# FMC_connector.net
KiCad netlist of a schematic drawn in Altium Designer
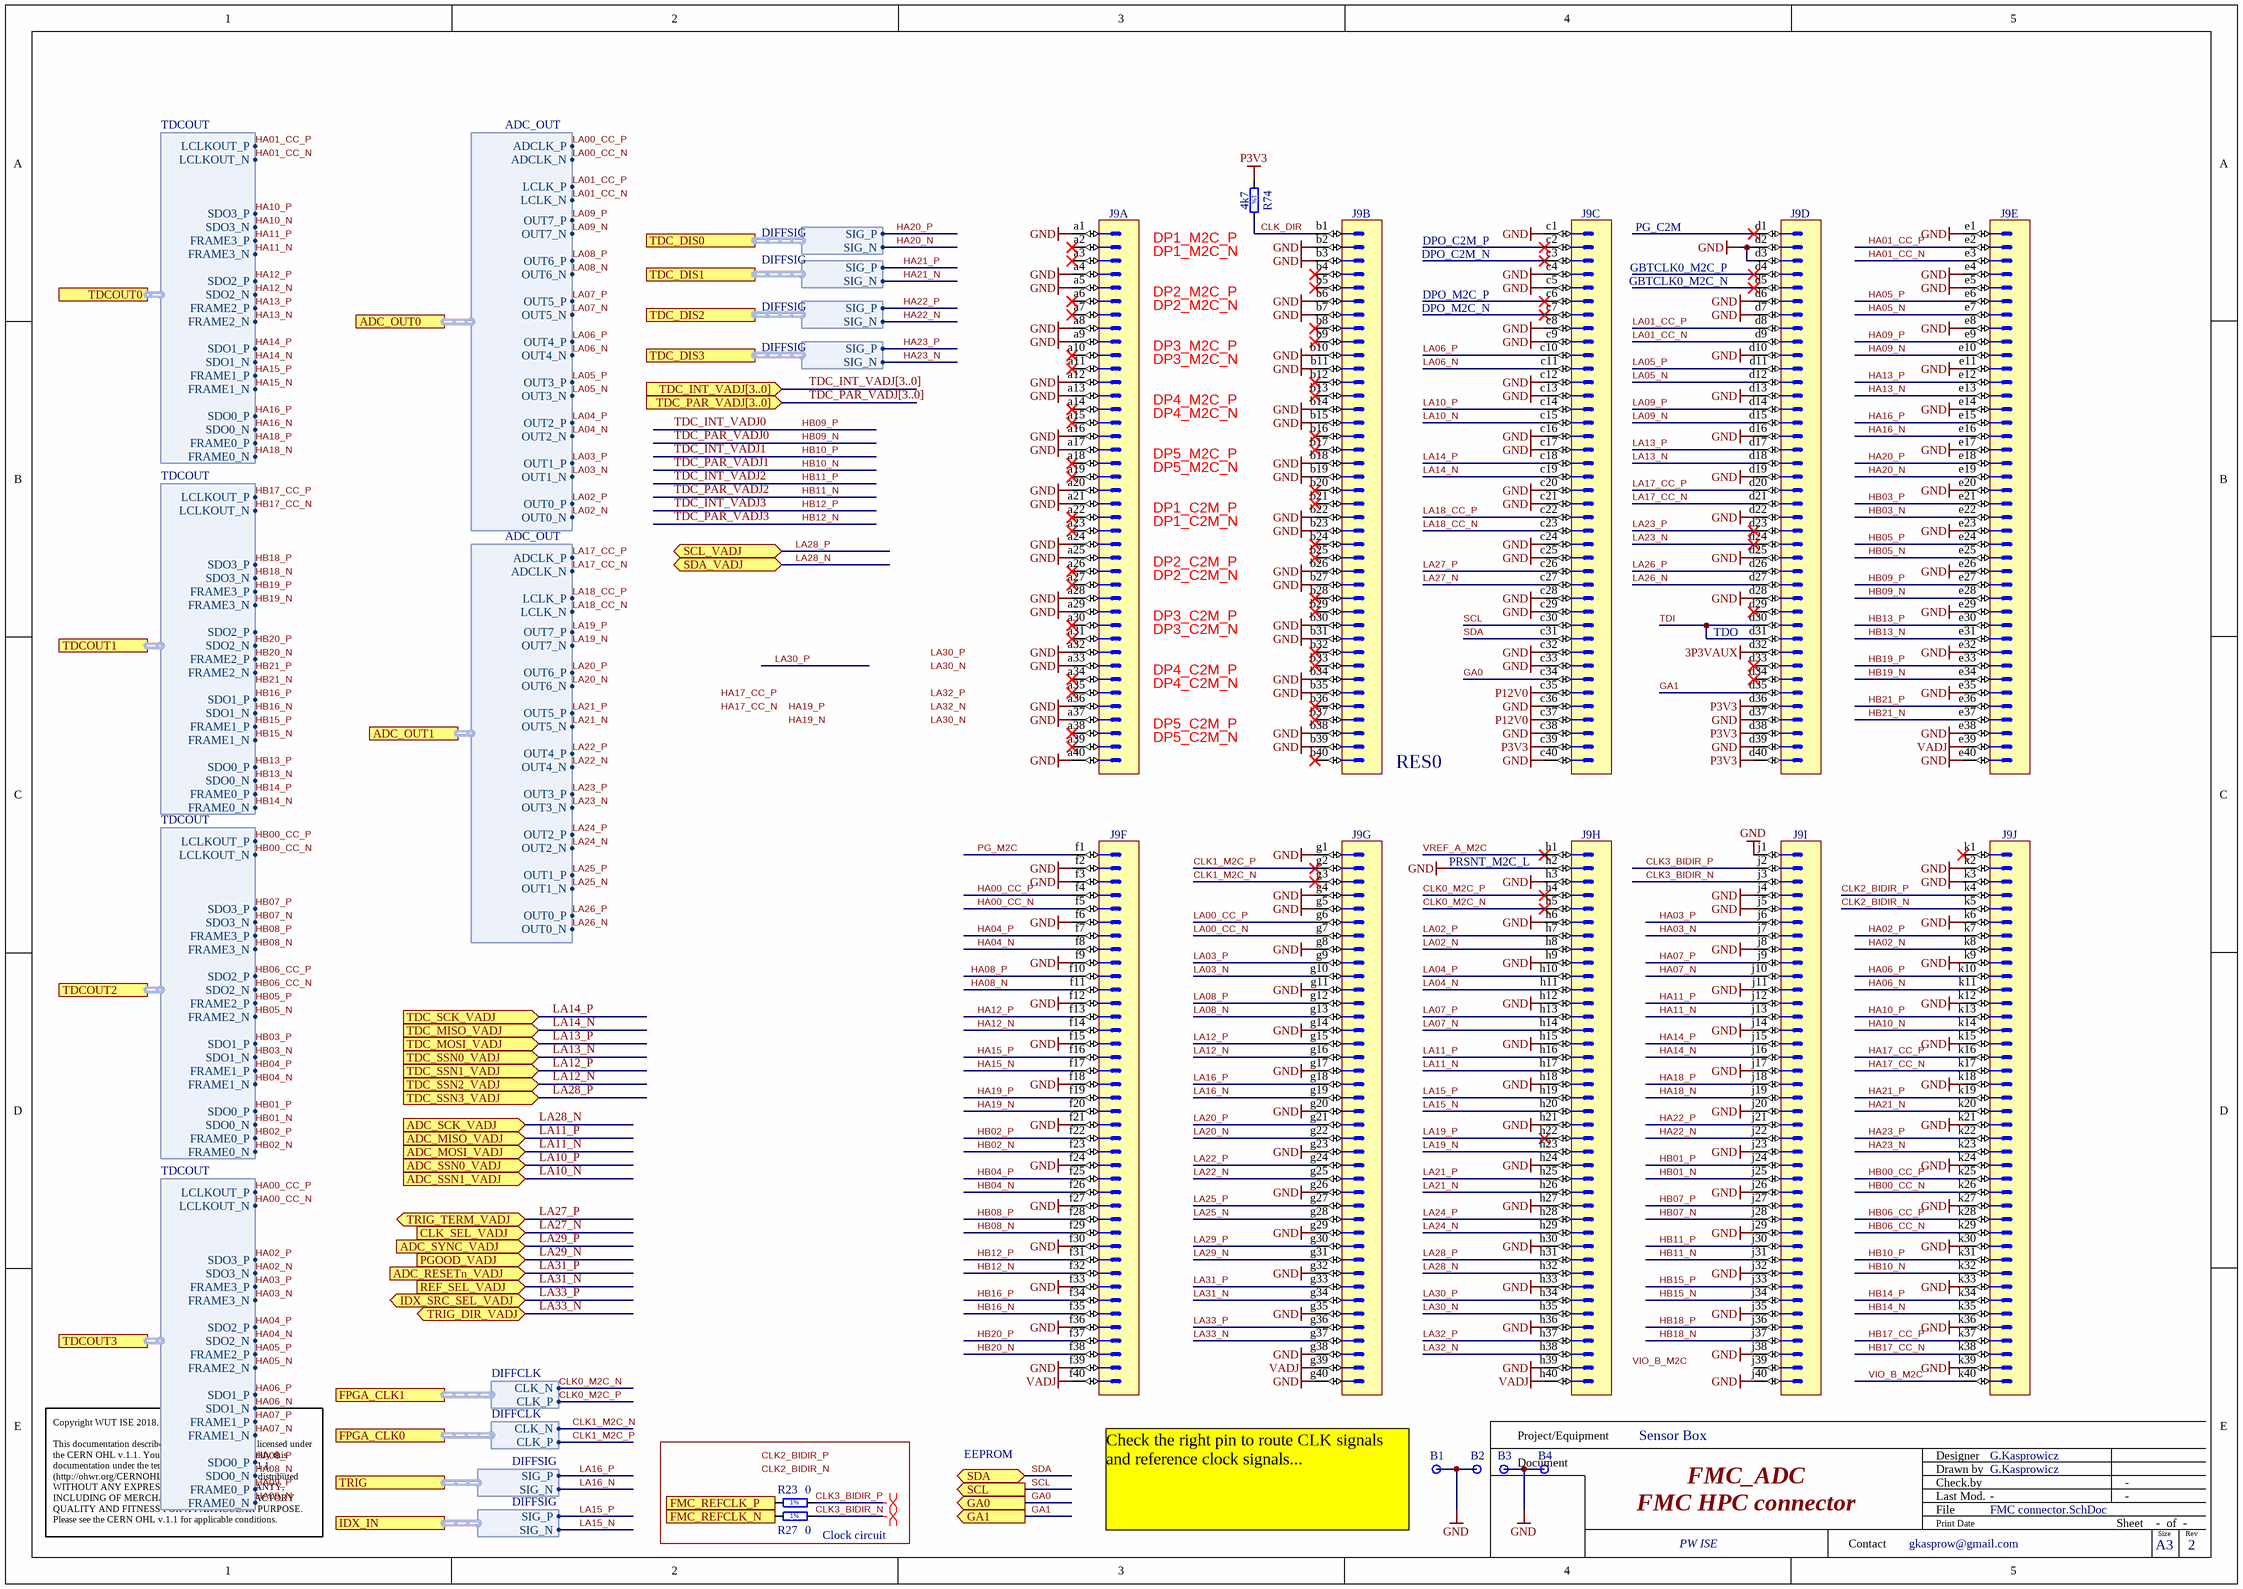
[diagram p0: FMC connector.SchDoc]

(export (version "E")
  (design (tool "Eeschema 10.0.6"))
  (components
    (comp (ref "B1")
      (value "Plated Hole")
      (footprint "MTG300_600")
      (description "Single Terminal Socket")
      (fields (field (name "PART NUMBER") "PLATED_HOLE3.0_PAD6.0") (field (name "AUTHOR") "CERN DEM JLC"))
      (libsource (lib "Eletro-mechanical") (part "Single Terminal Socket"))
    )
    (comp (ref "B2")
      (value "Plated Hole")
      (footprint "MTG300_600")
      (description "Single Terminal Socket")
      (fields (field (name "PART NUMBER") "PLATED_HOLE3.0_PAD6.0") (field (name "AUTHOR") "CERN DEM JLC"))
      (libsource (lib "Eletro-mechanical") (part "Single Terminal Socket"))
    )
    (comp (ref "B3")
      (value "Plated Hole")
      (footprint "MTG300_600")
      (description "Single Terminal Socket")
      (fields (field (name "PART NUMBER") "PLATED_HOLE3.0_PAD6.0") (field (name "AUTHOR") "CERN DEM JLC"))
      (libsource (lib "Eletro-mechanical") (part "Single Terminal Socket"))
    )
    (comp (ref "B4")
      (value "Plated Hole")
      (footprint "MTG300_600")
      (description "Single Terminal Socket")
      (fields (field (name "PART NUMBER") "PLATED_HOLE3.0_PAD6.0") (field (name "AUTHOR") "CERN DEM JLC"))
      (libsource (lib "Eletro-mechanical") (part "Single Terminal Socket"))
    )
    (comp (ref "J9")
      (value "VITA 57")
      (footprint "SAMTEC_ASP-134488-01")
      (description "Connector VITA 57, 400 Male contacts in 10 row abcdefghj")
      (fields
        (field (name "PART NUMBER") "SAMTEC_ASP-134488-01")
        (field (name "MANUFACTURER") "SAMTEC")
        (field (name "AUTHOR") "CERN DEM JLC")
      )
      (libsource (lib "Connectors") (part "Connector VITA 57 400 Male (abcdefghjk)"))
    )
    (comp (ref "R23")
      (value "0")
      (footprint "RESC1005X40N")
      (description "Resistor - 1%")
      (fields
        (field (name "PART NUMBER") "R0402_0R_JUMPER")
        (field (name "MANUFACTURER") "GENERIC")
        (field (name "AUTHOR") "CERN DEM JLC")
      )
      (libsource (lib "Resistors") (part "Resistor - 1%"))
    )
    (comp (ref "R27")
      (value "0")
      (footprint "RESC1005X40N")
      (description "Resistor - 1%")
      (fields
        (field (name "PART NUMBER") "R0402_0R_JUMPER")
        (field (name "MANUFACTURER") "GENERIC")
        (field (name "AUTHOR") "CERN DEM JLC")
      )
      (libsource (lib "Resistors") (part "Resistor - 1%"))
    )
    (comp (ref "R74")
      (value "4k7")
      (footprint "RESC1608X55N")
      (description "Resistor - 1%")
      (fields
        (field (name "PART NUMBER") "R0603_4K7_1%_0.1W_100PPM")
        (field (name "POWER") "0.1W")
        (field (name "AUTHOR") "CERN DEM JLC")
      )
      (libsource (lib "Resistors") (part "Resistor - 1%"))
    )
  )
  (nets
    (net (code "5") (name "/CLK0_M2C_N") (class "Default")
      (node (ref "J9") (pin "h5") (pinfunction "h5_h5") (pintype "bidirectional"))
    )
    (net (code "6") (name "/CLK0_M2C_P") (class "Default")
      (node (ref "J9") (pin "h4") (pinfunction "h4_h4") (pintype "bidirectional+no_connect"))
    )
    (net (code "7") (name "/CLK1_M2C_N") (class "Default")
      (node (ref "J9") (pin "g3") (pinfunction "g3_g3") (pintype "bidirectional+no_connect"))
    )
    (net (code "8") (name "/CLK1_M2C_P") (class "Default")
      (node (ref "J9") (pin "g2") (pinfunction "g2_g2") (pintype "bidirectional+no_connect"))
    )
    (net (code "9") (name "/CLK2_BIDIR_N") (class "Default")
      (node (ref "J9") (pin "k5") (pinfunction "k5_k5") (pintype "bidirectional"))
    )
    (net (code "10") (name "/CLK2_BIDIR_P") (class "Default")
      (node (ref "J9") (pin "k4") (pinfunction "k4_k4") (pintype "bidirectional"))
    )
    (net (code "11") (name "/CLK3_BIDIR_N") (class "Default")
      (node (ref "J9") (pin "j3") (pinfunction "j3_j3") (pintype "bidirectional"))
      (node (ref "R27") (pin "2") (pinfunction "2_2") (pintype "passive"))
    )
    (net (code "12") (name "/CLK3_BIDIR_P") (class "Default")
      (node (ref "J9") (pin "j2") (pinfunction "j2_j2") (pintype "bidirectional"))
      (node (ref "R23") (pin "2") (pinfunction "2_2") (pintype "passive"))
    )
    (net (code "13") (name "/CLK_DIR") (class "Default")
      (node (ref "J9") (pin "b1") (pinfunction "b1_b1") (pintype "bidirectional"))
      (node (ref "R74") (pin "2") (pinfunction "2_2") (pintype "passive"))
    )
    (net (code "14") (name "/FMC_REFCLK_N") (class "Default")
      (node (ref "R27") (pin "1") (pinfunction "1_1") (pintype "passive"))
    )
    (net (code "15") (name "/FMC_REFCLK_P") (class "Default")
      (node (ref "R23") (pin "1") (pinfunction "1_1") (pintype "passive"))
    )
    (net (code "16") (name "/GA0") (class "Default")
      (node (ref "J9") (pin "c34") (pinfunction "c34_c34") (pintype "bidirectional"))
    )
    (net (code "17") (name "/GA1") (class "Default")
      (node (ref "J9") (pin "d35") (pinfunction "d35_d35") (pintype "bidirectional"))
    )
    (net (code "18") (name "/HA00_CC_N") (class "Default")
      (node (ref "J9") (pin "f5") (pinfunction "f5_f5") (pintype "bidirectional"))
    )
    (net (code "19") (name "/HA00_CC_P") (class "Default")
      (node (ref "J9") (pin "f4") (pinfunction "f4_f4") (pintype "bidirectional"))
    )
    (net (code "20") (name "/HA01_CC_N") (class "Default")
      (node (ref "J9") (pin "e3") (pinfunction "e3_e3") (pintype "bidirectional"))
    )
    (net (code "21") (name "/HA01_CC_P") (class "Default")
      (node (ref "J9") (pin "e2") (pinfunction "e2_e2") (pintype "bidirectional"))
    )
    (net (code "22") (name "/HA02_N") (class "Default")
      (node (ref "J9") (pin "k8") (pinfunction "k8_k8") (pintype "bidirectional"))
    )
    (net (code "23") (name "/HA02_P") (class "Default")
      (node (ref "J9") (pin "k7") (pinfunction "k7_k7") (pintype "bidirectional"))
    )
    (net (code "24") (name "/HA03_N") (class "Default")
      (node (ref "J9") (pin "j7") (pinfunction "j7_j7") (pintype "bidirectional"))
    )
    (net (code "25") (name "/HA03_P") (class "Default")
      (node (ref "J9") (pin "j6") (pinfunction "j6_j6") (pintype "bidirectional"))
    )
    (net (code "26") (name "/HA04_N") (class "Default")
      (node (ref "J9") (pin "f8") (pinfunction "f8_f8") (pintype "bidirectional"))
    )
    (net (code "27") (name "/HA04_P") (class "Default")
      (node (ref "J9") (pin "f7") (pinfunction "f7_f7") (pintype "bidirectional"))
    )
    (net (code "28") (name "/HA05_N") (class "Default")
      (node (ref "J9") (pin "e7") (pinfunction "e7_e7") (pintype "bidirectional"))
    )
    (net (code "29") (name "/HA05_P") (class "Default")
      (node (ref "J9") (pin "e6") (pinfunction "e6_e6") (pintype "bidirectional"))
    )
    (net (code "30") (name "/HA06_N") (class "Default")
      (node (ref "J9") (pin "k11") (pinfunction "k11_k11") (pintype "bidirectional"))
    )
    (net (code "31") (name "/HA06_P") (class "Default")
      (node (ref "J9") (pin "k10") (pinfunction "k10_k10") (pintype "bidirectional"))
    )
    (net (code "32") (name "/HA07_N") (class "Default")
      (node (ref "J9") (pin "j10") (pinfunction "j10_j10") (pintype "bidirectional"))
    )
    (net (code "33") (name "/HA07_P") (class "Default")
      (node (ref "J9") (pin "j9") (pinfunction "j9_j9") (pintype "bidirectional"))
    )
    (net (code "34") (name "/HA08_N") (class "Default")
      (node (ref "J9") (pin "f11") (pinfunction "f11_f11") (pintype "bidirectional"))
    )
    (net (code "35") (name "/HA08_P") (class "Default")
      (node (ref "J9") (pin "f10") (pinfunction "f10_f10") (pintype "bidirectional"))
    )
    (net (code "36") (name "/HA09_N") (class "Default")
      (node (ref "J9") (pin "e10") (pinfunction "e10_e10") (pintype "bidirectional"))
    )
    (net (code "37") (name "/HA09_P") (class "Default")
      (node (ref "J9") (pin "e9") (pinfunction "e9_e9") (pintype "bidirectional"))
    )
    (net (code "38") (name "/HA10_N") (class "Default")
      (node (ref "J9") (pin "k14") (pinfunction "k14_k14") (pintype "bidirectional"))
    )
    (net (code "39") (name "/HA10_P") (class "Default")
      (node (ref "J9") (pin "k13") (pinfunction "k13_k13") (pintype "bidirectional"))
    )
    (net (code "40") (name "/HA11_N") (class "Default")
      (node (ref "J9") (pin "j13") (pinfunction "j13_j13") (pintype "bidirectional"))
    )
    (net (code "41") (name "/HA11_P") (class "Default")
      (node (ref "J9") (pin "j12") (pinfunction "j12_j12") (pintype "bidirectional"))
    )
    (net (code "42") (name "/HA12_N") (class "Default")
      (node (ref "J9") (pin "f14") (pinfunction "f14_f14") (pintype "bidirectional"))
    )
    (net (code "43") (name "/HA12_P") (class "Default")
      (node (ref "J9") (pin "f13") (pinfunction "f13_f13") (pintype "bidirectional"))
    )
    (net (code "44") (name "/HA13_N") (class "Default")
      (node (ref "J9") (pin "e13") (pinfunction "e13_e13") (pintype "bidirectional"))
    )
    (net (code "45") (name "/HA13_P") (class "Default")
      (node (ref "J9") (pin "e12") (pinfunction "e12_e12") (pintype "bidirectional"))
    )
    (net (code "46") (name "/HA14_N") (class "Default")
      (node (ref "J9") (pin "j16") (pinfunction "j16_j16") (pintype "bidirectional"))
    )
    (net (code "47") (name "/HA14_P") (class "Default")
      (node (ref "J9") (pin "j15") (pinfunction "j15_j15") (pintype "bidirectional"))
    )
    (net (code "48") (name "/HA15_N") (class "Default")
      (node (ref "J9") (pin "f17") (pinfunction "f17_f17") (pintype "bidirectional"))
    )
    (net (code "49") (name "/HA15_P") (class "Default")
      (node (ref "J9") (pin "f16") (pinfunction "f16_f16") (pintype "bidirectional"))
    )
    (net (code "50") (name "/HA16_N") (class "Default")
      (node (ref "J9") (pin "e16") (pinfunction "e16_e16") (pintype "bidirectional"))
    )
    (net (code "51") (name "/HA16_P") (class "Default")
      (node (ref "J9") (pin "e15") (pinfunction "e15_e15") (pintype "bidirectional"))
    )
    (net (code "52") (name "/HA17_CC_N") (class "Default")
      (node (ref "J9") (pin "k17") (pinfunction "k17_k17") (pintype "bidirectional"))
    )
    (net (code "53") (name "/HA17_CC_P") (class "Default")
      (node (ref "J9") (pin "k16") (pinfunction "k16_k16") (pintype "bidirectional"))
    )
    (net (code "54") (name "/HA18_N") (class "Default")
      (node (ref "J9") (pin "j19") (pinfunction "j19_j19") (pintype "bidirectional"))
    )
    (net (code "55") (name "/HA18_P") (class "Default")
      (node (ref "J9") (pin "j18") (pinfunction "j18_j18") (pintype "bidirectional"))
    )
    (net (code "56") (name "/HA19_N") (class "Default")
      (node (ref "J9") (pin "f20") (pinfunction "f20_f20") (pintype "bidirectional"))
    )
    (net (code "57") (name "/HA19_P") (class "Default")
      (node (ref "J9") (pin "f19") (pinfunction "f19_f19") (pintype "bidirectional"))
    )
    (net (code "58") (name "/HA20_N") (class "Default")
      (node (ref "J9") (pin "e19") (pinfunction "e19_e19") (pintype "bidirectional"))
    )
    (net (code "59") (name "/HA20_P") (class "Default")
      (node (ref "J9") (pin "e18") (pinfunction "e18_e18") (pintype "bidirectional"))
    )
    (net (code "60") (name "/HA21_N") (class "Default")
      (node (ref "J9") (pin "k20") (pinfunction "k20_k20") (pintype "bidirectional"))
    )
    (net (code "61") (name "/HA21_P") (class "Default")
      (node (ref "J9") (pin "k19") (pinfunction "k19_k19") (pintype "bidirectional"))
    )
    (net (code "62") (name "/HA22_N") (class "Default")
      (node (ref "J9") (pin "j22") (pinfunction "j22_j22") (pintype "bidirectional"))
    )
    (net (code "63") (name "/HA22_P") (class "Default")
      (node (ref "J9") (pin "j21") (pinfunction "j21_j21") (pintype "bidirectional"))
    )
    (net (code "64") (name "/HA23_N") (class "Default")
      (node (ref "J9") (pin "k23") (pinfunction "k23_k23") (pintype "bidirectional"))
    )
    (net (code "65") (name "/HA23_P") (class "Default")
      (node (ref "J9") (pin "k22") (pinfunction "k22_k22") (pintype "bidirectional"))
    )
    (net (code "66") (name "/HB00_CC_N") (class "Default")
      (node (ref "J9") (pin "k26") (pinfunction "k26_k26") (pintype "bidirectional"))
    )
    (net (code "67") (name "/HB00_CC_P") (class "Default")
      (node (ref "J9") (pin "k25") (pinfunction "k25_k25") (pintype "bidirectional"))
    )
    (net (code "68") (name "/HB01_N") (class "Default")
      (node (ref "J9") (pin "j25") (pinfunction "j25_j25") (pintype "bidirectional"))
    )
    (net (code "69") (name "/HB01_P") (class "Default")
      (node (ref "J9") (pin "j24") (pinfunction "j24_j24") (pintype "bidirectional"))
    )
    (net (code "70") (name "/HB02_N") (class "Default")
      (node (ref "J9") (pin "f23") (pinfunction "f23_f23") (pintype "bidirectional"))
    )
    (net (code "71") (name "/HB02_P") (class "Default")
      (node (ref "J9") (pin "f22") (pinfunction "f22_f22") (pintype "bidirectional"))
    )
    (net (code "72") (name "/HB03_N") (class "Default")
      (node (ref "J9") (pin "e22") (pinfunction "e22_e22") (pintype "bidirectional"))
    )
    (net (code "73") (name "/HB03_P") (class "Default")
      (node (ref "J9") (pin "e21") (pinfunction "e21_e21") (pintype "bidirectional"))
    )
    (net (code "74") (name "/HB04_N") (class "Default")
      (node (ref "J9") (pin "f26") (pinfunction "f26_f26") (pintype "bidirectional"))
    )
    (net (code "75") (name "/HB04_P") (class "Default")
      (node (ref "J9") (pin "f25") (pinfunction "f25_f25") (pintype "bidirectional"))
    )
    (net (code "76") (name "/HB05_N") (class "Default")
      (node (ref "J9") (pin "e25") (pinfunction "e25_e25") (pintype "bidirectional"))
    )
    (net (code "77") (name "/HB05_P") (class "Default")
      (node (ref "J9") (pin "e24") (pinfunction "e24_e24") (pintype "bidirectional"))
    )
    (net (code "78") (name "/HB06_CC_N") (class "Default")
      (node (ref "J9") (pin "k29") (pinfunction "k29_k29") (pintype "bidirectional"))
    )
    (net (code "79") (name "/HB06_CC_P") (class "Default")
      (node (ref "J9") (pin "k28") (pinfunction "k28_k28") (pintype "bidirectional"))
    )
    (net (code "80") (name "/HB07_N") (class "Default")
      (node (ref "J9") (pin "j28") (pinfunction "j28_j28") (pintype "bidirectional"))
    )
    (net (code "81") (name "/HB07_P") (class "Default")
      (node (ref "J9") (pin "j27") (pinfunction "j27_j27") (pintype "bidirectional"))
    )
    (net (code "82") (name "/HB08_N") (class "Default")
      (node (ref "J9") (pin "f29") (pinfunction "f29_f29") (pintype "bidirectional"))
    )
    (net (code "83") (name "/HB08_P") (class "Default")
      (node (ref "J9") (pin "f28") (pinfunction "f28_f28") (pintype "bidirectional"))
    )
    (net (code "84") (name "/HB13_N") (class "Default")
      (node (ref "J9") (pin "e31") (pinfunction "e31_e31") (pintype "bidirectional"))
    )
    (net (code "85") (name "/HB13_P") (class "Default")
      (node (ref "J9") (pin "e30") (pinfunction "e30_e30") (pintype "bidirectional"))
    )
    (net (code "86") (name "/HB14_N") (class "Default")
      (node (ref "J9") (pin "k35") (pinfunction "k35_k35") (pintype "bidirectional"))
    )
    (net (code "87") (name "/HB14_P") (class "Default")
      (node (ref "J9") (pin "k34") (pinfunction "k34_k34") (pintype "bidirectional"))
    )
    (net (code "88") (name "/HB15_N") (class "Default")
      (node (ref "J9") (pin "j34") (pinfunction "j34_j34") (pintype "bidirectional"))
    )
    (net (code "89") (name "/HB15_P") (class "Default")
      (node (ref "J9") (pin "j33") (pinfunction "j33_j33") (pintype "bidirectional"))
    )
    (net (code "90") (name "/HB16_N") (class "Default")
      (node (ref "J9") (pin "f35") (pinfunction "f35_f35") (pintype "bidirectional"))
    )
    (net (code "91") (name "/HB16_P") (class "Default")
      (node (ref "J9") (pin "f34") (pinfunction "f34_f34") (pintype "bidirectional"))
    )
    (net (code "92") (name "/HB17_CC_N") (class "Default")
      (node (ref "J9") (pin "k38") (pinfunction "k38_k38") (pintype "bidirectional"))
    )
    (net (code "93") (name "/HB17_CC_P") (class "Default")
      (node (ref "J9") (pin "k37") (pinfunction "k37_k37") (pintype "bidirectional"))
    )
    (net (code "94") (name "/HB18_N") (class "Default")
      (node (ref "J9") (pin "j37") (pinfunction "j37_j37") (pintype "bidirectional"))
    )
    (net (code "95") (name "/HB18_P") (class "Default")
      (node (ref "J9") (pin "j36") (pinfunction "j36_j36") (pintype "bidirectional"))
    )
    (net (code "96") (name "/HB19_N") (class "Default")
      (node (ref "J9") (pin "e34") (pinfunction "e34_e34") (pintype "bidirectional"))
    )
    (net (code "97") (name "/HB19_P") (class "Default")
      (node (ref "J9") (pin "e33") (pinfunction "e33_e33") (pintype "bidirectional"))
    )
    (net (code "98") (name "/HB20_N") (class "Default")
      (node (ref "J9") (pin "f38") (pinfunction "f38_f38") (pintype "bidirectional"))
    )
    (net (code "99") (name "/HB20_P") (class "Default")
      (node (ref "J9") (pin "f37") (pinfunction "f37_f37") (pintype "bidirectional"))
    )
    (net (code "100") (name "/HB21_N") (class "Default")
      (node (ref "J9") (pin "e37") (pinfunction "e37_e37") (pintype "bidirectional"))
    )
    (net (code "101") (name "/HB21_P") (class "Default")
      (node (ref "J9") (pin "e36") (pinfunction "e36_e36") (pintype "bidirectional"))
    )
    (net (code "102") (name "/LA00_CC_N") (class "Default")
      (node (ref "J9") (pin "g7") (pinfunction "g7_g7") (pintype "bidirectional"))
    )
    (net (code "103") (name "/LA00_CC_P") (class "Default")
      (node (ref "J9") (pin "g6") (pinfunction "g6_g6") (pintype "bidirectional"))
    )
    (net (code "104") (name "/LA01_CC_N") (class "Default")
      (node (ref "J9") (pin "d9") (pinfunction "d9_d9") (pintype "bidirectional"))
    )
    (net (code "105") (name "/LA01_CC_P") (class "Default")
      (node (ref "J9") (pin "d8") (pinfunction "d8_d8") (pintype "bidirectional"))
    )
    (net (code "106") (name "/LA02_N") (class "Default")
      (node (ref "J9") (pin "h8") (pinfunction "h8_h8") (pintype "bidirectional"))
    )
    (net (code "107") (name "/LA02_P") (class "Default")
      (node (ref "J9") (pin "h7") (pinfunction "h7_h7") (pintype "bidirectional"))
    )
    (net (code "108") (name "/LA03_N") (class "Default")
      (node (ref "J9") (pin "g10") (pinfunction "g10_g10") (pintype "bidirectional"))
    )
    (net (code "109") (name "/LA03_P") (class "Default")
      (node (ref "J9") (pin "g9") (pinfunction "g9_g9") (pintype "bidirectional"))
    )
    (net (code "110") (name "/LA04_N") (class "Default")
      (node (ref "J9") (pin "h11") (pinfunction "h11_h11") (pintype "bidirectional"))
    )
    (net (code "111") (name "/LA04_P") (class "Default")
      (node (ref "J9") (pin "h10") (pinfunction "h10_h10") (pintype "bidirectional"))
    )
    (net (code "112") (name "/LA05_N") (class "Default")
      (node (ref "J9") (pin "d12") (pinfunction "d12_d12") (pintype "bidirectional"))
    )
    (net (code "113") (name "/LA05_P") (class "Default")
      (node (ref "J9") (pin "d11") (pinfunction "d11_d11") (pintype "bidirectional"))
    )
    (net (code "114") (name "/LA06_N") (class "Default")
      (node (ref "J9") (pin "c11") (pinfunction "c11_c11") (pintype "bidirectional"))
    )
    (net (code "115") (name "/LA06_P") (class "Default")
      (node (ref "J9") (pin "c10") (pinfunction "c10_c10") (pintype "bidirectional"))
    )
    (net (code "116") (name "/LA07_N") (class "Default")
      (node (ref "J9") (pin "h14") (pinfunction "h14_h14") (pintype "bidirectional"))
    )
    (net (code "117") (name "/LA07_P") (class "Default")
      (node (ref "J9") (pin "h13") (pinfunction "h13_h13") (pintype "bidirectional"))
    )
    (net (code "118") (name "/LA08_N") (class "Default")
      (node (ref "J9") (pin "g13") (pinfunction "g13_g13") (pintype "bidirectional"))
    )
    (net (code "119") (name "/LA08_P") (class "Default")
      (node (ref "J9") (pin "g12") (pinfunction "g12_g12") (pintype "bidirectional"))
    )
    (net (code "120") (name "/LA09_N") (class "Default")
      (node (ref "J9") (pin "d15") (pinfunction "d15_d15") (pintype "bidirectional"))
    )
    (net (code "121") (name "/LA09_P") (class "Default")
      (node (ref "J9") (pin "d14") (pinfunction "d14_d14") (pintype "bidirectional"))
    )
    (net (code "122") (name "/LA10_N") (class "Default")
      (node (ref "J9") (pin "c15") (pinfunction "c15_c15") (pintype "bidirectional"))
    )
    (net (code "123") (name "/LA10_P") (class "Default")
      (node (ref "J9") (pin "c14") (pinfunction "c14_c14") (pintype "bidirectional"))
    )
    (net (code "124") (name "/LA11_N") (class "Default")
      (node (ref "J9") (pin "h17") (pinfunction "h17_h17") (pintype "bidirectional"))
    )
    (net (code "125") (name "/LA11_P") (class "Default")
      (node (ref "J9") (pin "h16") (pinfunction "h16_h16") (pintype "bidirectional"))
    )
    (net (code "126") (name "/LA12_N") (class "Default")
      (node (ref "J9") (pin "g16") (pinfunction "g16_g16") (pintype "bidirectional"))
    )
    (net (code "127") (name "/LA12_P") (class "Default")
      (node (ref "J9") (pin "g15") (pinfunction "g15_g15") (pintype "bidirectional"))
    )
    (net (code "128") (name "/LA13_N") (class "Default")
      (node (ref "J9") (pin "d18") (pinfunction "d18_d18") (pintype "bidirectional"))
    )
    (net (code "129") (name "/LA13_P") (class "Default")
      (node (ref "J9") (pin "d17") (pinfunction "d17_d17") (pintype "bidirectional"))
    )
    (net (code "130") (name "/LA14_N") (class "Default")
      (node (ref "J9") (pin "c19") (pinfunction "c19_c19") (pintype "bidirectional"))
    )
    (net (code "131") (name "/LA14_P") (class "Default")
      (node (ref "J9") (pin "c18") (pinfunction "c18_c18") (pintype "bidirectional"))
    )
    (net (code "132") (name "/LA15_N") (class "Default")
      (node (ref "J9") (pin "h20") (pinfunction "h20_h20") (pintype "bidirectional"))
    )
    (net (code "133") (name "/LA15_P") (class "Default")
      (node (ref "J9") (pin "h19") (pinfunction "h19_h19") (pintype "bidirectional"))
    )
    (net (code "134") (name "/LA16_N") (class "Default")
      (node (ref "J9") (pin "g19") (pinfunction "g19_g19") (pintype "bidirectional"))
    )
    (net (code "135") (name "/LA16_P") (class "Default")
      (node (ref "J9") (pin "g18") (pinfunction "g18_g18") (pintype "bidirectional"))
    )
    (net (code "136") (name "/LA17_CC_N") (class "Default")
      (node (ref "J9") (pin "d21") (pinfunction "d21_d21") (pintype "bidirectional"))
    )
    (net (code "137") (name "/LA17_CC_P") (class "Default")
      (node (ref "J9") (pin "d20") (pinfunction "d20_d20") (pintype "bidirectional"))
    )
    (net (code "138") (name "/LA18_CC_N") (class "Default")
      (node (ref "J9") (pin "c23") (pinfunction "c23_c23") (pintype "bidirectional"))
    )
    (net (code "139") (name "/LA18_CC_P") (class "Default")
      (node (ref "J9") (pin "c22") (pinfunction "c22_c22") (pintype "bidirectional"))
    )
    (net (code "140") (name "/LA19_N") (class "Default")
      (node (ref "J9") (pin "h23") (pinfunction "h23_h23") (pintype "bidirectional"))
    )
    (net (code "141") (name "/LA19_P") (class "Default")
      (node (ref "J9") (pin "h22") (pinfunction "h22_h22") (pintype "bidirectional"))
    )
    (net (code "142") (name "/LA20_N") (class "Default")
      (node (ref "J9") (pin "g22") (pinfunction "g22_g22") (pintype "bidirectional"))
    )
    (net (code "143") (name "/LA20_P") (class "Default")
      (node (ref "J9") (pin "g21") (pinfunction "g21_g21") (pintype "bidirectional"))
    )
    (net (code "144") (name "/LA21_N") (class "Default")
      (node (ref "J9") (pin "h26") (pinfunction "h26_h26") (pintype "bidirectional"))
    )
    (net (code "145") (name "/LA21_P") (class "Default")
      (node (ref "J9") (pin "h25") (pinfunction "h25_h25") (pintype "bidirectional"))
    )
    (net (code "146") (name "/LA22_N") (class "Default")
      (node (ref "J9") (pin "g25") (pinfunction "g25_g25") (pintype "bidirectional"))
    )
    (net (code "147") (name "/LA22_P") (class "Default")
      (node (ref "J9") (pin "g24") (pinfunction "g24_g24") (pintype "bidirectional"))
    )
    (net (code "148") (name "/LA23_N") (class "Default")
      (node (ref "J9") (pin "d24") (pinfunction "d24_d24") (pintype "bidirectional+no_connect"))
    )
    (net (code "149") (name "/LA23_P") (class "Default")
      (node (ref "J9") (pin "d23") (pinfunction "d23_d23") (pintype "bidirectional+no_connect"))
    )
    (net (code "150") (name "/LA24_N") (class "Default")
      (node (ref "J9") (pin "h29") (pinfunction "h29_h29") (pintype "bidirectional"))
    )
    (net (code "151") (name "/LA24_P") (class "Default")
      (node (ref "J9") (pin "h28") (pinfunction "h28_h28") (pintype "bidirectional"))
    )
    (net (code "152") (name "/LA25_N") (class "Default")
      (node (ref "J9") (pin "g28") (pinfunction "g28_g28") (pintype "bidirectional"))
    )
    (net (code "153") (name "/LA25_P") (class "Default")
      (node (ref "J9") (pin "g27") (pinfunction "g27_g27") (pintype "bidirectional"))
    )
    (net (code "154") (name "/LA26_N") (class "Default")
      (node (ref "J9") (pin "d27") (pinfunction "d27_d27") (pintype "bidirectional"))
    )
    (net (code "155") (name "/LA26_P") (class "Default")
      (node (ref "J9") (pin "d26") (pinfunction "d26_d26") (pintype "bidirectional"))
    )
    (net (code "156") (name "/LA27_N") (class "Default")
      (node (ref "J9") (pin "c27") (pinfunction "c27_c27") (pintype "bidirectional"))
    )
    (net (code "157") (name "/LA27_P") (class "Default")
      (node (ref "J9") (pin "c26") (pinfunction "c26_c26") (pintype "bidirectional"))
    )
    (net (code "158") (name "/LA28_N") (class "Default")
      (node (ref "J9") (pin "h32") (pinfunction "h32_h32") (pintype "bidirectional"))
    )
    (net (code "159") (name "/LA28_P") (class "Default")
      (node (ref "J9") (pin "h31") (pinfunction "h31_h31") (pintype "bidirectional"))
    )
    (net (code "160") (name "/LA29_N") (class "Default")
      (node (ref "J9") (pin "g31") (pinfunction "g31_g31") (pintype "bidirectional"))
    )
    (net (code "161") (name "/LA29_P") (class "Default")
      (node (ref "J9") (pin "g30") (pinfunction "g30_g30") (pintype "bidirectional"))
    )
    (net (code "162") (name "/LA30_N") (class "Default")
      (node (ref "J9") (pin "h35") (pinfunction "h35_h35") (pintype "bidirectional"))
    )
    (net (code "163") (name "/LA30_P") (class "Default")
      (node (ref "J9") (pin "h34") (pinfunction "h34_h34") (pintype "bidirectional"))
    )
    (net (code "164") (name "/LA31_N") (class "Default")
      (node (ref "J9") (pin "g34") (pinfunction "g34_g34") (pintype "bidirectional"))
    )
    (net (code "165") (name "/LA31_P") (class "Default")
      (node (ref "J9") (pin "g33") (pinfunction "g33_g33") (pintype "bidirectional"))
    )
    (net (code "166") (name "/LA32_N") (class "Default")
      (node (ref "J9") (pin "h38") (pinfunction "h38_h38") (pintype "bidirectional"))
    )
    (net (code "167") (name "/LA32_P") (class "Default")
      (node (ref "J9") (pin "h37") (pinfunction "h37_h37") (pintype "bidirectional"))
    )
    (net (code "168") (name "/LA33_N") (class "Default")
      (node (ref "J9") (pin "g37") (pinfunction "g37_g37") (pintype "bidirectional"))
    )
    (net (code "169") (name "/LA33_P") (class "Default")
      (node (ref "J9") (pin "g36") (pinfunction "g36_g36") (pintype "bidirectional"))
    )
    (net (code "170") (name "/PG_M2C") (class "Default")
      (node (ref "J9") (pin "f1") (pinfunction "f1_f1") (pintype "bidirectional"))
    )
    (net (code "171") (name "/SCL") (class "Default")
      (node (ref "J9") (pin "c30") (pinfunction "c30_c30") (pintype "bidirectional"))
    )
    (net (code "172") (name "/SDA") (class "Default")
      (node (ref "J9") (pin "c31") (pinfunction "c31_c31") (pintype "bidirectional"))
    )
    (net (code "173") (name "/TDC_INT_VADJ0") (class "Default")
      (node (ref "J9") (pin "e27") (pinfunction "e27_e27") (pintype "bidirectional"))
    )
    (net (code "174") (name "/TDC_INT_VADJ1") (class "Default")
      (node (ref "J9") (pin "k31") (pinfunction "k31_k31") (pintype "bidirectional"))
    )
    (net (code "175") (name "/TDC_INT_VADJ2") (class "Default")
      (node (ref "J9") (pin "j30") (pinfunction "j30_j30") (pintype "bidirectional"))
    )
    (net (code "176") (name "/TDC_INT_VADJ3") (class "Default")
      (node (ref "J9") (pin "f31") (pinfunction "f31_f31") (pintype "bidirectional"))
    )
    (net (code "178") (name "/TDC_PAR_VADJ0") (class "Default")
      (node (ref "J9") (pin "e28") (pinfunction "e28_e28") (pintype "bidirectional"))
    )
    (net (code "179") (name "/TDC_PAR_VADJ1") (class "Default")
      (node (ref "J9") (pin "k32") (pinfunction "k32_k32") (pintype "bidirectional"))
    )
    (net (code "180") (name "/TDC_PAR_VADJ2") (class "Default")
      (node (ref "J9") (pin "j31") (pinfunction "j31_j31") (pintype "bidirectional"))
    )
    (net (code "181") (name "/TDC_PAR_VADJ3") (class "Default")
      (node (ref "J9") (pin "f32") (pinfunction "f32_f32") (pintype "bidirectional"))
    )
    (net (code "183") (name "/TDI") (class "Default")
      (node (ref "J9") (pin "d30") (pinfunction "d30_d30") (pintype "bidirectional"))
      (node (ref "J9") (pin "d31") (pinfunction "d31_d31") (pintype "bidirectional"))
    )
    (net (code "184") (name "/VIO_B_M2C") (class "Default")
      (node (ref "J9") (pin "k40") (pinfunction "k40_k40") (pintype "bidirectional"))
    )
    (net (code "185") (name "/VREF_A_M2C") (class "Default")
      (node (ref "J9") (pin "h1") (pinfunction "h1_h1") (pintype "bidirectional+no_connect"))
    )
    (net (code "190") (name "3P3VAUX") (class "Default")
      (node (ref "J9") (pin "d32") (pinfunction "d32_d32") (pintype "bidirectional"))
    )
    (net (code "191") (name "GND") (class "Default")
      (node (ref "B1") (pin "1") (pinfunction "1_1") (pintype "bidirectional"))
      (node (ref "B2") (pin "1") (pinfunction "1_1") (pintype "bidirectional"))
      (node (ref "B3") (pin "1") (pinfunction "1_1") (pintype "bidirectional"))
      (node (ref "B4") (pin "1") (pinfunction "1_1") (pintype "bidirectional"))
      (node (ref "J9") (pin "a1") (pinfunction "a1_a1") (pintype "bidirectional"))
      (node (ref "J9") (pin "a12") (pinfunction "a12_a12") (pintype "bidirectional"))
      (node (ref "J9") (pin "a13") (pinfunction "a13_a13") (pintype "bidirectional"))
      (node (ref "J9") (pin "a16") (pinfunction "a16_a16") (pintype "bidirectional"))
      (node (ref "J9") (pin "a17") (pinfunction "a17_a17") (pintype "bidirectional"))
      (node (ref "J9") (pin "a20") (pinfunction "a20_a20") (pintype "bidirectional"))
      (node (ref "J9") (pin "a21") (pinfunction "a21_a21") (pintype "bidirectional"))
      (node (ref "J9") (pin "a24") (pinfunction "a24_a24") (pintype "bidirectional"))
      (node (ref "J9") (pin "a25") (pinfunction "a25_a25") (pintype "bidirectional"))
      (node (ref "J9") (pin "a28") (pinfunction "a28_a28") (pintype "bidirectional"))
      (node (ref "J9") (pin "a29") (pinfunction "a29_a29") (pintype "bidirectional"))
      (node (ref "J9") (pin "a32") (pinfunction "a32_a32") (pintype "bidirectional"))
      (node (ref "J9") (pin "a33") (pinfunction "a33_a33") (pintype "bidirectional"))
      (node (ref "J9") (pin "a36") (pinfunction "a36_a36") (pintype "bidirectional"))
      (node (ref "J9") (pin "a37") (pinfunction "a37_a37") (pintype "bidirectional"))
      (node (ref "J9") (pin "a4") (pinfunction "a4_a4") (pintype "bidirectional"))
      (node (ref "J9") (pin "a40") (pinfunction "a40_a40") (pintype "bidirectional"))
      (node (ref "J9") (pin "a5") (pinfunction "a5_a5") (pintype "bidirectional"))
      (node (ref "J9") (pin "a8") (pinfunction "a8_a8") (pintype "bidirectional"))
      (node (ref "J9") (pin "a9") (pinfunction "a9_a9") (pintype "bidirectional"))
      (node (ref "J9") (pin "b10") (pinfunction "b10_b10") (pintype "bidirectional"))
      (node (ref "J9") (pin "b11") (pinfunction "b11_b11") (pintype "bidirectional"))
      (node (ref "J9") (pin "b14") (pinfunction "b14_b14") (pintype "bidirectional"))
      (node (ref "J9") (pin "b15") (pinfunction "b15_b15") (pintype "bidirectional"))
      (node (ref "J9") (pin "b18") (pinfunction "b18_b18") (pintype "bidirectional"))
      (node (ref "J9") (pin "b19") (pinfunction "b19_b19") (pintype "bidirectional"))
      (node (ref "J9") (pin "b2") (pinfunction "b2_b2") (pintype "bidirectional"))
      (node (ref "J9") (pin "b22") (pinfunction "b22_b22") (pintype "bidirectional"))
      (node (ref "J9") (pin "b23") (pinfunction "b23_b23") (pintype "bidirectional"))
      (node (ref "J9") (pin "b26") (pinfunction "b26_b26") (pintype "bidirectional"))
      (node (ref "J9") (pin "b27") (pinfunction "b27_b27") (pintype "bidirectional"))
      (node (ref "J9") (pin "b3") (pinfunction "b3_b3") (pintype "bidirectional"))
      (node (ref "J9") (pin "b30") (pinfunction "b30_b30") (pintype "bidirectional"))
      (node (ref "J9") (pin "b31") (pinfunction "b31_b31") (pintype "bidirectional"))
      (node (ref "J9") (pin "b34") (pinfunction "b34_b34") (pintype "bidirectional"))
      (node (ref "J9") (pin "b35") (pinfunction "b35_b35") (pintype "bidirectional"))
      (node (ref "J9") (pin "b38") (pinfunction "b38_b38") (pintype "bidirectional"))
      (node (ref "J9") (pin "b39") (pinfunction "b39_b39") (pintype "bidirectional"))
      (node (ref "J9") (pin "b6") (pinfunction "b6_b6") (pintype "bidirectional"))
      (node (ref "J9") (pin "b7") (pinfunction "b7_b7") (pintype "bidirectional"))
      (node (ref "J9") (pin "c1") (pinfunction "c1_c1") (pintype "bidirectional"))
      (node (ref "J9") (pin "c12") (pinfunction "c12_c12") (pintype "bidirectional"))
      (node (ref "J9") (pin "c13") (pinfunction "c13_c13") (pintype "bidirectional"))
      (node (ref "J9") (pin "c16") (pinfunction "c16_c16") (pintype "bidirectional"))
      (node (ref "J9") (pin "c17") (pinfunction "c17_c17") (pintype "bidirectional"))
      (node (ref "J9") (pin "c20") (pinfunction "c20_c20") (pintype "bidirectional"))
      (node (ref "J9") (pin "c21") (pinfunction "c21_c21") (pintype "bidirectional"))
      (node (ref "J9") (pin "c24") (pinfunction "c24_c24") (pintype "bidirectional"))
      (node (ref "J9") (pin "c25") (pinfunction "c25_c25") (pintype "bidirectional"))
      (node (ref "J9") (pin "c28") (pinfunction "c28_c28") (pintype "bidirectional"))
      (node (ref "J9") (pin "c29") (pinfunction "c29_c29") (pintype "bidirectional"))
      (node (ref "J9") (pin "c32") (pinfunction "c32_c32") (pintype "bidirectional"))
      (node (ref "J9") (pin "c33") (pinfunction "c33_c33") (pintype "bidirectional"))
      (node (ref "J9") (pin "c36") (pinfunction "c36_c36") (pintype "bidirectional"))
      (node (ref "J9") (pin "c38") (pinfunction "c38_c38") (pintype "bidirectional"))
      (node (ref "J9") (pin "c4") (pinfunction "c4_c4") (pintype "bidirectional"))
      (node (ref "J9") (pin "c40") (pinfunction "c40_c40") (pintype "bidirectional"))
      (node (ref "J9") (pin "c5") (pinfunction "c5_c5") (pintype "bidirectional"))
      (node (ref "J9") (pin "c8") (pinfunction "c8_c8") (pintype "bidirectional"))
      (node (ref "J9") (pin "c9") (pinfunction "c9_c9") (pintype "bidirectional"))
      (node (ref "J9") (pin "d10") (pinfunction "d10_d10") (pintype "bidirectional"))
      (node (ref "J9") (pin "d13") (pinfunction "d13_d13") (pintype "bidirectional"))
      (node (ref "J9") (pin "d16") (pinfunction "d16_d16") (pintype "bidirectional"))
      (node (ref "J9") (pin "d19") (pinfunction "d19_d19") (pintype "bidirectional"))
      (node (ref "J9") (pin "d2") (pinfunction "d2_d2") (pintype "bidirectional"))
      (node (ref "J9") (pin "d22") (pinfunction "d22_d22") (pintype "bidirectional"))
      (node (ref "J9") (pin "d25") (pinfunction "d25_d25") (pintype "bidirectional"))
      (node (ref "J9") (pin "d28") (pinfunction "d28_d28") (pintype "bidirectional"))
      (node (ref "J9") (pin "d3") (pinfunction "d3_d3") (pintype "bidirectional"))
      (node (ref "J9") (pin "d37") (pinfunction "d37_d37") (pintype "bidirectional"))
      (node (ref "J9") (pin "d39") (pinfunction "d39_d39") (pintype "bidirectional"))
      (node (ref "J9") (pin "d6") (pinfunction "d6_d6") (pintype "bidirectional"))
      (node (ref "J9") (pin "d7") (pinfunction "d7_d7") (pintype "bidirectional"))
      (node (ref "J9") (pin "e1") (pinfunction "e1_e1") (pintype "bidirectional"))
      (node (ref "J9") (pin "e11") (pinfunction "e11_e11") (pintype "bidirectional"))
      (node (ref "J9") (pin "e14") (pinfunction "e14_e14") (pintype "bidirectional"))
      (node (ref "J9") (pin "e17") (pinfunction "e17_e17") (pintype "bidirectional"))
      (node (ref "J9") (pin "e20") (pinfunction "e20_e20") (pintype "bidirectional"))
      (node (ref "J9") (pin "e23") (pinfunction "e23_e23") (pintype "bidirectional"))
      (node (ref "J9") (pin "e26") (pinfunction "e26_e26") (pintype "bidirectional"))
      (node (ref "J9") (pin "e29") (pinfunction "e29_e29") (pintype "bidirectional"))
      (node (ref "J9") (pin "e32") (pinfunction "e32_e32") (pintype "bidirectional"))
      (node (ref "J9") (pin "e35") (pinfunction "e35_e35") (pintype "bidirectional"))
      (node (ref "J9") (pin "e38") (pinfunction "e38_e38") (pintype "bidirectional"))
      (node (ref "J9") (pin "e4") (pinfunction "e4_e4") (pintype "bidirectional"))
      (node (ref "J9") (pin "e40") (pinfunction "e40_e40") (pintype "bidirectional"))
      (node (ref "J9") (pin "e5") (pinfunction "e5_e5") (pintype "bidirectional"))
      (node (ref "J9") (pin "e8") (pinfunction "e8_e8") (pintype "bidirectional"))
      (node (ref "J9") (pin "f12") (pinfunction "f12_f12") (pintype "bidirectional"))
      (node (ref "J9") (pin "f15") (pinfunction "f15_f15") (pintype "bidirectional"))
      (node (ref "J9") (pin "f18") (pinfunction "f18_f18") (pintype "bidirectional"))
      (node (ref "J9") (pin "f2") (pinfunction "f2_f2") (pintype "bidirectional"))
      (node (ref "J9") (pin "f21") (pinfunction "f21_f21") (pintype "bidirectional"))
      (node (ref "J9") (pin "f24") (pinfunction "f24_f24") (pintype "bidirectional"))
      (node (ref "J9") (pin "f27") (pinfunction "f27_f27") (pintype "bidirectional"))
      (node (ref "J9") (pin "f3") (pinfunction "f3_f3") (pintype "bidirectional"))
      (node (ref "J9") (pin "f30") (pinfunction "f30_f30") (pintype "bidirectional"))
      (node (ref "J9") (pin "f33") (pinfunction "f33_f33") (pintype "bidirectional"))
      (node (ref "J9") (pin "f36") (pinfunction "f36_f36") (pintype "bidirectional"))
      (node (ref "J9") (pin "f39") (pinfunction "f39_f39") (pintype "bidirectional"))
      (node (ref "J9") (pin "f6") (pinfunction "f6_f6") (pintype "bidirectional"))
      (node (ref "J9") (pin "f9") (pinfunction "f9_f9") (pintype "bidirectional"))
      (node (ref "J9") (pin "g1") (pinfunction "g1_g1") (pintype "bidirectional"))
      (node (ref "J9") (pin "g11") (pinfunction "g11_g11") (pintype "bidirectional"))
      (node (ref "J9") (pin "g14") (pinfunction "g14_g14") (pintype "bidirectional"))
      (node (ref "J9") (pin "g17") (pinfunction "g17_g17") (pintype "bidirectional"))
      (node (ref "J9") (pin "g20") (pinfunction "g20_g20") (pintype "bidirectional"))
      (node (ref "J9") (pin "g23") (pinfunction "g23_g23") (pintype "bidirectional"))
      (node (ref "J9") (pin "g26") (pinfunction "g26_g26") (pintype "bidirectional"))
      (node (ref "J9") (pin "g29") (pinfunction "g29_g29") (pintype "bidirectional"))
      (node (ref "J9") (pin "g32") (pinfunction "g32_g32") (pintype "bidirectional"))
      (node (ref "J9") (pin "g35") (pinfunction "g35_g35") (pintype "bidirectional"))
      (node (ref "J9") (pin "g38") (pinfunction "g38_g38") (pintype "bidirectional"))
      (node (ref "J9") (pin "g4") (pinfunction "g4_g4") (pintype "bidirectional"))
      (node (ref "J9") (pin "g40") (pinfunction "g40_g40") (pintype "bidirectional"))
      (node (ref "J9") (pin "g5") (pinfunction "g5_g5") (pintype "bidirectional"))
      (node (ref "J9") (pin "g8") (pinfunction "g8_g8") (pintype "bidirectional"))
      (node (ref "J9") (pin "h12") (pinfunction "h12_h12") (pintype "bidirectional"))
      (node (ref "J9") (pin "h15") (pinfunction "h15_h15") (pintype "bidirectional"))
      (node (ref "J9") (pin "h18") (pinfunction "h18_h18") (pintype "bidirectional"))
      (node (ref "J9") (pin "h2") (pinfunction "h2_h2") (pintype "bidirectional"))
      (node (ref "J9") (pin "h21") (pinfunction "h21_h21") (pintype "bidirectional"))
      (node (ref "J9") (pin "h24") (pinfunction "h24_h24") (pintype "bidirectional"))
      (node (ref "J9") (pin "h27") (pinfunction "h27_h27") (pintype "bidirectional"))
      (node (ref "J9") (pin "h3") (pinfunction "h3_h3") (pintype "bidirectional"))
      (node (ref "J9") (pin "h30") (pinfunction "h30_h30") (pintype "bidirectional"))
      (node (ref "J9") (pin "h33") (pinfunction "h33_h33") (pintype "bidirectional"))
      (node (ref "J9") (pin "h36") (pinfunction "h36_h36") (pintype "bidirectional"))
      (node (ref "J9") (pin "h39") (pinfunction "h39_h39") (pintype "bidirectional"))
      (node (ref "J9") (pin "h6") (pinfunction "h6_h6") (pintype "bidirectional"))
      (node (ref "J9") (pin "h9") (pinfunction "h9_h9") (pintype "bidirectional"))
      (node (ref "J9") (pin "j1") (pinfunction "j1_j1") (pintype "bidirectional"))
      (node (ref "J9") (pin "j11") (pinfunction "j11_j11") (pintype "bidirectional"))
      (node (ref "J9") (pin "j14") (pinfunction "j14_j14") (pintype "bidirectional"))
      (node (ref "J9") (pin "j17") (pinfunction "j17_j17") (pintype "bidirectional"))
      (node (ref "J9") (pin "j20") (pinfunction "j20_j20") (pintype "bidirectional"))
      (node (ref "J9") (pin "j23") (pinfunction "j23_j23") (pintype "bidirectional"))
      (node (ref "J9") (pin "j26") (pinfunction "j26_j26") (pintype "bidirectional"))
      (node (ref "J9") (pin "j29") (pinfunction "j29_j29") (pintype "bidirectional"))
      (node (ref "J9") (pin "j32") (pinfunction "j32_j32") (pintype "bidirectional"))
      (node (ref "J9") (pin "j35") (pinfunction "j35_j35") (pintype "bidirectional"))
      (node (ref "J9") (pin "j38") (pinfunction "j38_j38") (pintype "bidirectional"))
      (node (ref "J9") (pin "j4") (pinfunction "j4_j4") (pintype "bidirectional"))
      (node (ref "J9") (pin "j40") (pinfunction "j40_j40") (pintype "bidirectional"))
      (node (ref "J9") (pin "j5") (pinfunction "j5_j5") (pintype "bidirectional"))
      (node (ref "J9") (pin "j8") (pinfunction "j8_j8") (pintype "bidirectional"))
      (node (ref "J9") (pin "k12") (pinfunction "k12_k12") (pintype "bidirectional"))
      (node (ref "J9") (pin "k15") (pinfunction "k15_k15") (pintype "bidirectional"))
      (node (ref "J9") (pin "k18") (pinfunction "k18_k18") (pintype "bidirectional"))
      (node (ref "J9") (pin "k2") (pinfunction "k2_k2") (pintype "bidirectional"))
      (node (ref "J9") (pin "k21") (pinfunction "k21_k21") (pintype "bidirectional"))
      (node (ref "J9") (pin "k24") (pinfunction "k24_k24") (pintype "bidirectional"))
      (node (ref "J9") (pin "k27") (pinfunction "k27_k27") (pintype "bidirectional"))
      (node (ref "J9") (pin "k3") (pinfunction "k3_k3") (pintype "bidirectional"))
      (node (ref "J9") (pin "k30") (pinfunction "k30_k30") (pintype "bidirectional"))
      (node (ref "J9") (pin "k33") (pinfunction "k33_k33") (pintype "bidirectional"))
      (node (ref "J9") (pin "k36") (pinfunction "k36_k36") (pintype "bidirectional"))
      (node (ref "J9") (pin "k39") (pinfunction "k39_k39") (pintype "bidirectional"))
      (node (ref "J9") (pin "k6") (pinfunction "k6_k6") (pintype "bidirectional"))
      (node (ref "J9") (pin "k9") (pinfunction "k9_k9") (pintype "bidirectional"))
    )
    (net (code "192") (name "P3V3") (class "Default")
      (node (ref "J9") (pin "c39") (pinfunction "c39_c39") (pintype "bidirectional"))
      (node (ref "J9") (pin "d36") (pinfunction "d36_d36") (pintype "bidirectional"))
      (node (ref "J9") (pin "d38") (pinfunction "d38_d38") (pintype "bidirectional"))
      (node (ref "J9") (pin "d40") (pinfunction "d40_d40") (pintype "bidirectional"))
      (node (ref "R74") (pin "1") (pinfunction "1_1") (pintype "passive"))
    )
    (net (code "193") (name "P12V0") (class "Default")
      (node (ref "J9") (pin "c35") (pinfunction "c35_c35") (pintype "bidirectional"))
      (node (ref "J9") (pin "c37") (pinfunction "c37_c37") (pintype "bidirectional"))
    )
    (net (code "194") (name "VADJ") (class "Default")
      (node (ref "J9") (pin "e39") (pinfunction "e39_e39") (pintype "bidirectional"))
      (node (ref "J9") (pin "f40") (pinfunction "f40_f40") (pintype "bidirectional"))
      (node (ref "J9") (pin "g39") (pinfunction "g39_g39") (pintype "bidirectional"))
      (node (ref "J9") (pin "h40") (pinfunction "h40_h40") (pintype "bidirectional"))
    )
    (net (code "195") (name "unconnected-(J9-Pada2)") (class "Default")
      (node (ref "J9") (pin "a2") (pinfunction "a2_a2") (pintype "bidirectional+no_connect"))
    )
    (net (code "196") (name "unconnected-(J9-Pada3)") (class "Default")
      (node (ref "J9") (pin "a3") (pinfunction "a3_a3") (pintype "bidirectional+no_connect"))
    )
    (net (code "197") (name "unconnected-(J9-Pada6)") (class "Default")
      (node (ref "J9") (pin "a6") (pinfunction "a6_a6") (pintype "bidirectional+no_connect"))
    )
    (net (code "198") (name "unconnected-(J9-Pada7)") (class "Default")
      (node (ref "J9") (pin "a7") (pinfunction "a7_a7") (pintype "bidirectional+no_connect"))
    )
    (net (code "199") (name "unconnected-(J9-Pada10)") (class "Default")
      (node (ref "J9") (pin "a10") (pinfunction "a10_a10") (pintype "bidirectional+no_connect"))
    )
    (net (code "200") (name "unconnected-(J9-Pada11)") (class "Default")
      (node (ref "J9") (pin "a11") (pinfunction "a11_a11") (pintype "bidirectional+no_connect"))
    )
    (net (code "201") (name "unconnected-(J9-Pada14)") (class "Default")
      (node (ref "J9") (pin "a14") (pinfunction "a14_a14") (pintype "bidirectional+no_connect"))
    )
    (net (code "202") (name "unconnected-(J9-Pada15)") (class "Default")
      (node (ref "J9") (pin "a15") (pinfunction "a15_a15") (pintype "bidirectional+no_connect"))
    )
    (net (code "203") (name "unconnected-(J9-Pada18)") (class "Default")
      (node (ref "J9") (pin "a18") (pinfunction "a18_a18") (pintype "bidirectional+no_connect"))
    )
    (net (code "204") (name "unconnected-(J9-Pada19)") (class "Default")
      (node (ref "J9") (pin "a19") (pinfunction "a19_a19") (pintype "bidirectional+no_connect"))
    )
    (net (code "205") (name "unconnected-(J9-Pada22)") (class "Default")
      (node (ref "J9") (pin "a22") (pinfunction "a22_a22") (pintype "bidirectional+no_connect"))
    )
    (net (code "206") (name "unconnected-(J9-Pada23)") (class "Default")
      (node (ref "J9") (pin "a23") (pinfunction "a23_a23") (pintype "bidirectional+no_connect"))
    )
    (net (code "207") (name "unconnected-(J9-Pada26)") (class "Default")
      (node (ref "J9") (pin "a26") (pinfunction "a26_a26") (pintype "bidirectional+no_connect"))
    )
    (net (code "208") (name "unconnected-(J9-Pada27)") (class "Default")
      (node (ref "J9") (pin "a27") (pinfunction "a27_a27") (pintype "bidirectional+no_connect"))
    )
    (net (code "209") (name "unconnected-(J9-Pada30)") (class "Default")
      (node (ref "J9") (pin "a30") (pinfunction "a30_a30") (pintype "bidirectional+no_connect"))
    )
    (net (code "210") (name "unconnected-(J9-Pada31)") (class "Default")
      (node (ref "J9") (pin "a31") (pinfunction "a31_a31") (pintype "bidirectional+no_connect"))
    )
    (net (code "211") (name "unconnected-(J9-Pada34)") (class "Default")
      (node (ref "J9") (pin "a34") (pinfunction "a34_a34") (pintype "bidirectional+no_connect"))
    )
    (net (code "212") (name "unconnected-(J9-Pada35)") (class "Default")
      (node (ref "J9") (pin "a35") (pinfunction "a35_a35") (pintype "bidirectional+no_connect"))
    )
    (net (code "213") (name "unconnected-(J9-Pada38)") (class "Default")
      (node (ref "J9") (pin "a38") (pinfunction "a38_a38") (pintype "bidirectional+no_connect"))
    )
    (net (code "214") (name "unconnected-(J9-Pada39)") (class "Default")
      (node (ref "J9") (pin "a39") (pinfunction "a39_a39") (pintype "bidirectional+no_connect"))
    )
    (net (code "215") (name "unconnected-(J9-Padb4)") (class "Default")
      (node (ref "J9") (pin "b4") (pinfunction "b4_b4") (pintype "bidirectional+no_connect"))
    )
    (net (code "216") (name "unconnected-(J9-Padb5)") (class "Default")
      (node (ref "J9") (pin "b5") (pinfunction "b5_b5") (pintype "bidirectional+no_connect"))
    )
    (net (code "217") (name "unconnected-(J9-Padb8)") (class "Default")
      (node (ref "J9") (pin "b8") (pinfunction "b8_b8") (pintype "bidirectional+no_connect"))
    )
    (net (code "218") (name "unconnected-(J9-Padb9)") (class "Default")
      (node (ref "J9") (pin "b9") (pinfunction "b9_b9") (pintype "bidirectional+no_connect"))
    )
    (net (code "219") (name "unconnected-(J9-Padb12)") (class "Default")
      (node (ref "J9") (pin "b12") (pinfunction "b12_b12") (pintype "bidirectional+no_connect"))
    )
    (net (code "220") (name "unconnected-(J9-Padb13)") (class "Default")
      (node (ref "J9") (pin "b13") (pinfunction "b13_b13") (pintype "bidirectional+no_connect"))
    )
    (net (code "221") (name "unconnected-(J9-Padb16)") (class "Default")
      (node (ref "J9") (pin "b16") (pinfunction "b16_b16") (pintype "bidirectional+no_connect"))
    )
    (net (code "222") (name "unconnected-(J9-Padb17)") (class "Default")
      (node (ref "J9") (pin "b17") (pinfunction "b17_b17") (pintype "bidirectional+no_connect"))
    )
    (net (code "223") (name "unconnected-(J9-Padb20)") (class "Default")
      (node (ref "J9") (pin "b20") (pinfunction "b20_b20") (pintype "bidirectional+no_connect"))
    )
    (net (code "224") (name "unconnected-(J9-Padb21)") (class "Default")
      (node (ref "J9") (pin "b21") (pinfunction "b21_b21") (pintype "bidirectional+no_connect"))
    )
    (net (code "225") (name "unconnected-(J9-Padb24)") (class "Default")
      (node (ref "J9") (pin "b24") (pinfunction "b24_b24") (pintype "bidirectional+no_connect"))
    )
    (net (code "226") (name "unconnected-(J9-Padb25)") (class "Default")
      (node (ref "J9") (pin "b25") (pinfunction "b25_b25") (pintype "bidirectional+no_connect"))
    )
    (net (code "227") (name "unconnected-(J9-Padb28)") (class "Default")
      (node (ref "J9") (pin "b28") (pinfunction "b28_b28") (pintype "bidirectional+no_connect"))
    )
    (net (code "228") (name "unconnected-(J9-Padb29)") (class "Default")
      (node (ref "J9") (pin "b29") (pinfunction "b29_b29") (pintype "bidirectional+no_connect"))
    )
    (net (code "229") (name "unconnected-(J9-Padb32)") (class "Default")
      (node (ref "J9") (pin "b32") (pinfunction "b32_b32") (pintype "bidirectional+no_connect"))
    )
    (net (code "230") (name "unconnected-(J9-Padb33)") (class "Default")
      (node (ref "J9") (pin "b33") (pinfunction "b33_b33") (pintype "bidirectional+no_connect"))
    )
    (net (code "231") (name "unconnected-(J9-Padb36)") (class "Default")
      (node (ref "J9") (pin "b36") (pinfunction "b36_b36") (pintype "bidirectional+no_connect"))
    )
    (net (code "232") (name "unconnected-(J9-Padb37)") (class "Default")
      (node (ref "J9") (pin "b37") (pinfunction "b37_b37") (pintype "bidirectional+no_connect"))
    )
    (net (code "233") (name "unconnected-(J9-Padb40)") (class "Default")
      (node (ref "J9") (pin "b40") (pinfunction "b40_b40") (pintype "bidirectional+no_connect"))
    )
    (net (code "234") (name "unconnected-(J9-Padc2)") (class "Default")
      (node (ref "J9") (pin "c2") (pinfunction "c2_c2") (pintype "bidirectional+no_connect"))
    )
    (net (code "235") (name "unconnected-(J9-Padc3)") (class "Default")
      (node (ref "J9") (pin "c3") (pinfunction "c3_c3") (pintype "bidirectional+no_connect"))
    )
    (net (code "236") (name "unconnected-(J9-Padc6)") (class "Default")
      (node (ref "J9") (pin "c6") (pinfunction "c6_c6") (pintype "bidirectional+no_connect"))
    )
    (net (code "237") (name "unconnected-(J9-Padc7)") (class "Default")
      (node (ref "J9") (pin "c7") (pinfunction "c7_c7") (pintype "bidirectional+no_connect"))
    )
    (net (code "238") (name "unconnected-(J9-Padd1)") (class "Default")
      (node (ref "J9") (pin "d1") (pinfunction "d1_d1") (pintype "bidirectional+no_connect"))
    )
    (net (code "239") (name "unconnected-(J9-Padd4)") (class "Default")
      (node (ref "J9") (pin "d4") (pinfunction "d4_d4") (pintype "bidirectional+no_connect"))
    )
    (net (code "240") (name "unconnected-(J9-Padd5)") (class "Default")
      (node (ref "J9") (pin "d5") (pinfunction "d5_d5") (pintype "bidirectional+no_connect"))
    )
    (net (code "241") (name "unconnected-(J9-Padd29)") (class "Default")
      (node (ref "J9") (pin "d29") (pinfunction "d29_d29") (pintype "bidirectional+no_connect"))
    )
    (net (code "242") (name "unconnected-(J9-Padd33)") (class "Default")
      (node (ref "J9") (pin "d33") (pinfunction "d33_d33") (pintype "bidirectional+no_connect"))
    )
    (net (code "243") (name "unconnected-(J9-Padd34)") (class "Default")
      (node (ref "J9") (pin "d34") (pinfunction "d34_d34") (pintype "bidirectional+no_connect"))
    )
    (net (code "244") (name "unconnected-(J9-Padj39)") (class "Default")
      (node (ref "J9") (pin "j39") (pinfunction "j39_j39") (pintype "bidirectional"))
    )
    (net (code "245") (name "unconnected-(J9-Padk1)") (class "Default")
      (node (ref "J9") (pin "k1") (pinfunction "k1_k1") (pintype "bidirectional+no_connect"))
    )
  )
)
